# LnControlPanel.net
KiCad netlist of a schematic drawn in EAGLE
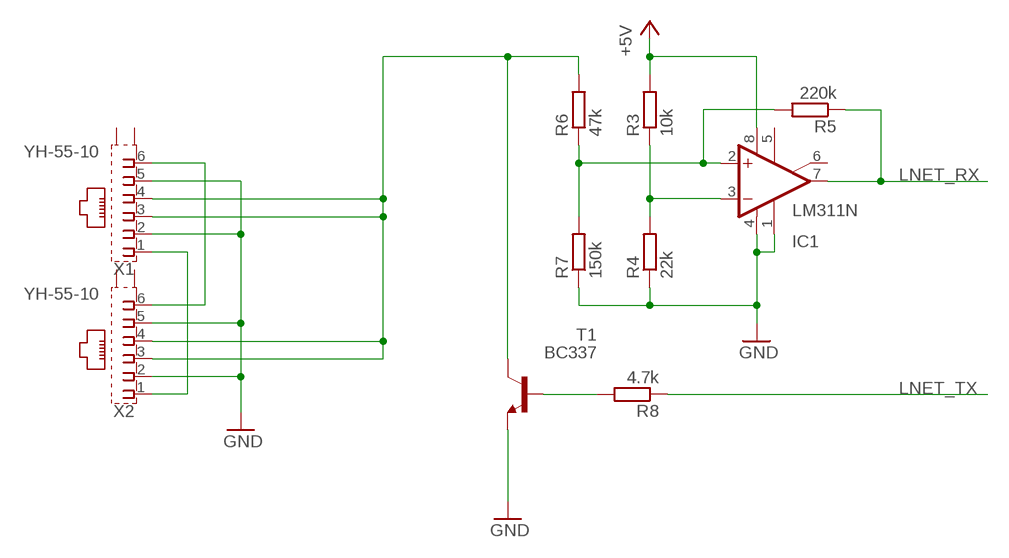
[diagram p0: schematic, sheet 1]
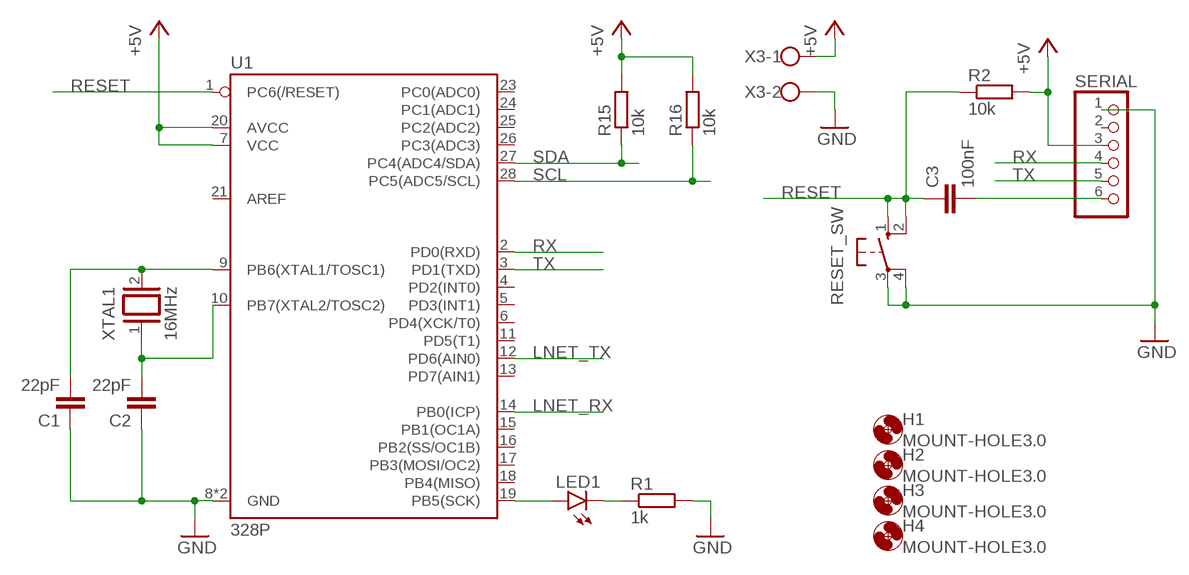
[diagram p1: schematic, sheet 2]
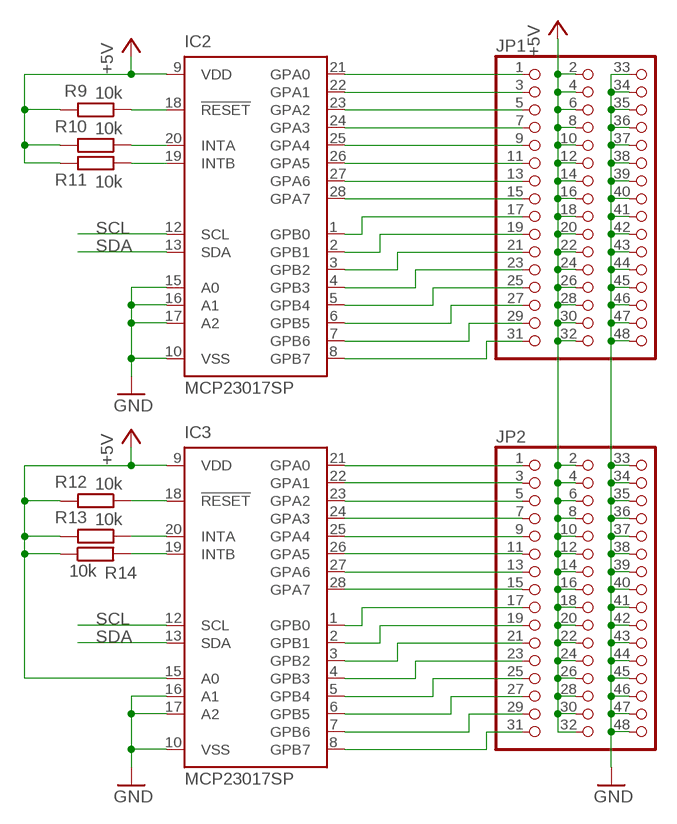
[diagram p2: schematic, sheet 3]

(export (version "E")
  (design (tool "Eeschema 10.0.6"))
  (components
    (comp (ref "C1")
      (value "22pF")
      (footprint "eagle-import:C025-025X050")
      (libsource (lib "eagle-import") (part "C-EU025-025X050"))
    )
    (comp (ref "C2")
      (value "22pF")
      (footprint "eagle-import:C025-025X050")
      (libsource (lib "eagle-import") (part "C-EU025-025X050"))
    )
    (comp (ref "C3")
      (value "100nF")
      (footprint "eagle-import:C050-030X075")
      (libsource (lib "eagle-import") (part "C-EU050-030X075"))
    )
    (comp (ref "H1")
      (value "MOUNT-HOLE3.0")
      (footprint "eagle-import:3,0")
      (libsource (lib "eagle-import") (part "MOUNT-HOLE3.0"))
    )
    (comp (ref "H2")
      (value "MOUNT-HOLE3.0")
      (footprint "eagle-import:3,0")
      (libsource (lib "eagle-import") (part "MOUNT-HOLE3.0"))
    )
    (comp (ref "H3")
      (value "MOUNT-HOLE3.0")
      (footprint "eagle-import:3,0")
      (libsource (lib "eagle-import") (part "MOUNT-HOLE3.0"))
    )
    (comp (ref "H4")
      (value "MOUNT-HOLE3.0")
      (footprint "eagle-import:3,0")
      (libsource (lib "eagle-import") (part "MOUNT-HOLE3.0"))
    )
    (comp (ref "LED1")
      (value "LED3MM")
      (footprint "eagle-import:LED3MM")
      (libsource (lib "eagle-import") (part "LED3MM"))
    )
    (comp (ref "R1")
      (value "1k")
      (footprint "eagle-import:0207_2V")
      (libsource (lib "eagle-import") (part "rcl_334_R-EU_0207/2V"))
    )
    (comp (ref "R2")
      (value "10k")
      (footprint "eagle-import:0207_2V")
      (libsource (lib "eagle-import") (part "rcl_334_R-EU_0207/2V"))
    )
    (comp (ref "R15")
      (value "10k")
      (footprint "eagle-import:0207_2V")
      (libsource (lib "eagle-import") (part "rcl_334_R-EU_0207/2V"))
    )
    (comp (ref "R16")
      (value "10k")
      (footprint "eagle-import:0207_2V")
      (libsource (lib "eagle-import") (part "rcl_334_R-EU_0207/2V"))
    )
    (comp (ref "RESET_SW")
      (value "10-XX")
      (footprint "eagle-import:B3F-10XX")
      (fields (field (name "MPN") "B3F-1000"))
      (libsource (lib "eagle-import") (part "10-XX"))
    )
    (comp (ref "SERIAL")
      (value "PINHD-1X6")
      (footprint "eagle-import:1X06")
      (libsource (lib "eagle-import") (part "PINHD-1X6"))
    )
    (comp (ref "U1")
      (value "328P")
      (footprint "eagle-import:DIP28")
      (libsource (lib "eagle-import") (part "ATMEGA328P_PDIP"))
    )
    (comp (ref "X3")
      (value "W237-102")
      (footprint "eagle-import:W237-102")
      (fields (field (name "MPN") "237-102"))
      (libsource (lib "eagle-import") (part "W237-102"))
    )
    (comp (ref "XTAL1")
      (value "16MHz")
      (footprint "eagle-import:QS")
      (libsource (lib "eagle-import") (part "XTAL/S"))
    )
    (comp (ref "IC2")
      (value "MCP23017SP")
      (footprint "eagle-import:DIL28-3")
      (fields (field (name "MF") "MICROCHIP") (field (name "MPN") "MCP23017-E/SP"))
      (libsource (lib "eagle-import") (part "MCP23017SP"))
    )
    (comp (ref "IC3")
      (value "MCP23017SP")
      (footprint "eagle-import:DIL28-3")
      (fields (field (name "MF") "MICROCHIP") (field (name "MPN") "MCP23017-E/SP"))
      (libsource (lib "eagle-import") (part "MCP23017SP"))
    )
    (comp (ref "JP1")
      (value "PINHD-3X16")
      (footprint "eagle-import:3X16")
      (libsource (lib "eagle-import") (part "PINHD-3X16"))
    )
    (comp (ref "JP2")
      (value "PINHD-3X16")
      (footprint "eagle-import:3X16")
      (libsource (lib "eagle-import") (part "PINHD-3X16"))
    )
    (comp (ref "R9")
      (value "10k")
      (footprint "eagle-import:0207_2V")
      (libsource (lib "eagle-import") (part "R-EU_0207/2V"))
    )
    (comp (ref "R10")
      (value "10k")
      (footprint "eagle-import:0207_2V")
      (libsource (lib "eagle-import") (part "R-EU_0207/2V"))
    )
    (comp (ref "R11")
      (value "10k")
      (footprint "eagle-import:0207_2V")
      (libsource (lib "eagle-import") (part "R-EU_0207/2V"))
    )
    (comp (ref "R12")
      (value "10k")
      (footprint "eagle-import:0207_2V")
      (libsource (lib "eagle-import") (part "R-EU_0207/2V"))
    )
    (comp (ref "R13")
      (value "10k")
      (footprint "eagle-import:0207_2V")
      (libsource (lib "eagle-import") (part "R-EU_0207/2V"))
    )
    (comp (ref "R14")
      (value "10k")
      (footprint "eagle-import:0207_2V")
      (libsource (lib "eagle-import") (part "R-EU_0207/2V"))
    )
    (comp (ref "IC1")
      (value "LM311N")
      (footprint "eagle-import:DIL08")
      (libsource (lib "eagle-import") (part "LM311N"))
    )
    (comp (ref "R3")
      (value "10k")
      (footprint "eagle-import:0207_2V")
      (libsource (lib "eagle-import") (part "R-EU_0207/2V"))
    )
    (comp (ref "R4")
      (value "22k")
      (footprint "eagle-import:0207_2V")
      (libsource (lib "eagle-import") (part "R-EU_0207/2V"))
    )
    (comp (ref "R5")
      (value "220k")
      (footprint "eagle-import:0207_2V")
      (libsource (lib "eagle-import") (part "R-EU_0207/2V"))
    )
    (comp (ref "R6")
      (value "47k")
      (footprint "eagle-import:0207_2V")
      (libsource (lib "eagle-import") (part "R-EU_0207/2V"))
    )
    (comp (ref "R7")
      (value "150k")
      (footprint "eagle-import:0207_2V")
      (libsource (lib "eagle-import") (part "R-EU_0207/2V"))
    )
    (comp (ref "R8")
      (value "4.7k")
      (footprint "eagle-import:0207_2V")
      (libsource (lib "eagle-import") (part "R-EU_0207/2V"))
    )
    (comp (ref "T1")
      (value "BC337")
      (footprint "eagle-import:TO92")
      (libsource (lib "eagle-import") (part "BC337"))
    )
    (comp (ref "X1")
      (value "YH-55-10")
      (footprint "eagle-import:YH-55-10")
      (libsource (lib "eagle-import") (part "YH-55-10"))
    )
    (comp (ref "X2")
      (value "YH-55-10")
      (footprint "eagle-import:YH-55-10")
      (libsource (lib "eagle-import") (part "YH-55-10"))
    )
  )
  (nets
    (net (code "1") (name "+5V") (class "Default")
      (node (ref "IC1") (pin "8") (pinfunction "V+_8") (pintype "power_in"))
      (node (ref "IC2") (pin "9") (pinfunction "VDD_9") (pintype "power_in"))
      (node (ref "IC3") (pin "15") (pinfunction "A0_15") (pintype "input"))
      (node (ref "IC3") (pin "9") (pinfunction "VDD_9") (pintype "power_in"))
      (node (ref "JP1") (pin "10") (pinfunction "10_10") (pintype "passive"))
      (node (ref "JP1") (pin "12") (pinfunction "12_12") (pintype "passive"))
      (node (ref "JP1") (pin "14") (pinfunction "14_14") (pintype "passive"))
      (node (ref "JP1") (pin "16") (pinfunction "16_16") (pintype "passive"))
      (node (ref "JP1") (pin "18") (pinfunction "18_18") (pintype "passive"))
      (node (ref "JP1") (pin "2") (pinfunction "2_2") (pintype "passive"))
      (node (ref "JP1") (pin "20") (pinfunction "20_20") (pintype "passive"))
      (node (ref "JP1") (pin "22") (pinfunction "22_22") (pintype "passive"))
      (node (ref "JP1") (pin "24") (pinfunction "24_24") (pintype "passive"))
      (node (ref "JP1") (pin "26") (pinfunction "26_26") (pintype "passive"))
      (node (ref "JP1") (pin "28") (pinfunction "28_28") (pintype "passive"))
      (node (ref "JP1") (pin "30") (pinfunction "30_30") (pintype "passive"))
      (node (ref "JP1") (pin "32") (pinfunction "32_32") (pintype "passive"))
      (node (ref "JP1") (pin "4") (pinfunction "4_4") (pintype "passive"))
      (node (ref "JP1") (pin "6") (pinfunction "6_6") (pintype "passive"))
      (node (ref "JP1") (pin "8") (pinfunction "8_8") (pintype "passive"))
      (node (ref "JP2") (pin "10") (pinfunction "10_10") (pintype "passive"))
      (node (ref "JP2") (pin "12") (pinfunction "12_12") (pintype "passive"))
      (node (ref "JP2") (pin "14") (pinfunction "14_14") (pintype "passive"))
      (node (ref "JP2") (pin "16") (pinfunction "16_16") (pintype "passive"))
      (node (ref "JP2") (pin "18") (pinfunction "18_18") (pintype "passive"))
      (node (ref "JP2") (pin "2") (pinfunction "2_2") (pintype "passive"))
      (node (ref "JP2") (pin "20") (pinfunction "20_20") (pintype "passive"))
      (node (ref "JP2") (pin "22") (pinfunction "22_22") (pintype "passive"))
      (node (ref "JP2") (pin "24") (pinfunction "24_24") (pintype "passive"))
      (node (ref "JP2") (pin "26") (pinfunction "26_26") (pintype "passive"))
      (node (ref "JP2") (pin "28") (pinfunction "28_28") (pintype "passive"))
      (node (ref "JP2") (pin "30") (pinfunction "30_30") (pintype "passive"))
      (node (ref "JP2") (pin "32") (pinfunction "32_32") (pintype "passive"))
      (node (ref "JP2") (pin "4") (pinfunction "4_4") (pintype "passive"))
      (node (ref "JP2") (pin "6") (pinfunction "6_6") (pintype "passive"))
      (node (ref "JP2") (pin "8") (pinfunction "8_8") (pintype "passive"))
      (node (ref "R10") (pin "2") (pinfunction "2_2") (pintype "passive"))
      (node (ref "R11") (pin "2") (pinfunction "2_2") (pintype "passive"))
      (node (ref "R12") (pin "2") (pinfunction "2_2") (pintype "passive"))
      (node (ref "R13") (pin "2") (pinfunction "2_2") (pintype "passive"))
      (node (ref "R14") (pin "1") (pinfunction "1_1") (pintype "passive"))
      (node (ref "R15") (pin "2") (pinfunction "2_2") (pintype "passive"))
      (node (ref "R16") (pin "2") (pinfunction "2_2") (pintype "passive"))
      (node (ref "R2") (pin "2") (pinfunction "2_2") (pintype "passive"))
      (node (ref "R3") (pin "2") (pinfunction "2_2") (pintype "passive"))
      (node (ref "R9") (pin "2") (pinfunction "2_2") (pintype "passive"))
      (node (ref "SERIAL") (pin "3") (pinfunction "3_3") (pintype "passive"))
      (node (ref "U1") (pin "20") (pinfunction "AVCC_20") (pintype "bidirectional"))
      (node (ref "U1") (pin "7") (pinfunction "VCC_7") (pintype "bidirectional"))
      (node (ref "X3") (pin "1") (pinfunction "KL_1") (pintype "passive"))
    )
    (net (code "2") (name "GND") (class "Default")
      (node (ref "C1") (pin "1") (pinfunction "1_1") (pintype "passive"))
      (node (ref "C2") (pin "1") (pinfunction "1_1") (pintype "passive"))
      (node (ref "IC1") (pin "1") (pinfunction "GND_1") (pintype "passive"))
      (node (ref "IC1") (pin "4") (pinfunction "V-_4") (pintype "power_in"))
      (node (ref "IC2") (pin "10") (pinfunction "VSS_10") (pintype "power_in"))
      (node (ref "IC2") (pin "15") (pinfunction "A0_15") (pintype "input"))
      (node (ref "IC2") (pin "16") (pinfunction "A1_16") (pintype "input"))
      (node (ref "IC2") (pin "17") (pinfunction "A2_17") (pintype "input"))
      (node (ref "IC3") (pin "10") (pinfunction "VSS_10") (pintype "power_in"))
      (node (ref "IC3") (pin "16") (pinfunction "A1_16") (pintype "input"))
      (node (ref "IC3") (pin "17") (pinfunction "A2_17") (pintype "input"))
      (node (ref "JP1") (pin "33") (pinfunction "33_33") (pintype "passive"))
      (node (ref "JP1") (pin "34") (pinfunction "34_34") (pintype "passive"))
      (node (ref "JP1") (pin "35") (pinfunction "35_35") (pintype "passive"))
      (node (ref "JP1") (pin "36") (pinfunction "36_36") (pintype "passive"))
      (node (ref "JP1") (pin "37") (pinfunction "37_37") (pintype "passive"))
      (node (ref "JP1") (pin "38") (pinfunction "38_38") (pintype "passive"))
      (node (ref "JP1") (pin "39") (pinfunction "39_39") (pintype "passive"))
      (node (ref "JP1") (pin "40") (pinfunction "40_40") (pintype "passive"))
      (node (ref "JP1") (pin "41") (pinfunction "41_41") (pintype "passive"))
      (node (ref "JP1") (pin "42") (pinfunction "42_42") (pintype "passive"))
      (node (ref "JP1") (pin "43") (pinfunction "43_43") (pintype "passive"))
      (node (ref "JP1") (pin "44") (pinfunction "44_44") (pintype "passive"))
      (node (ref "JP1") (pin "45") (pinfunction "45_45") (pintype "passive"))
      (node (ref "JP1") (pin "46") (pinfunction "46_46") (pintype "passive"))
      (node (ref "JP1") (pin "47") (pinfunction "47_47") (pintype "passive"))
      (node (ref "JP1") (pin "48") (pinfunction "48_48") (pintype "passive"))
      (node (ref "JP2") (pin "33") (pinfunction "33_33") (pintype "passive"))
      (node (ref "JP2") (pin "34") (pinfunction "34_34") (pintype "passive"))
      (node (ref "JP2") (pin "35") (pinfunction "35_35") (pintype "passive"))
      (node (ref "JP2") (pin "36") (pinfunction "36_36") (pintype "passive"))
      (node (ref "JP2") (pin "37") (pinfunction "37_37") (pintype "passive"))
      (node (ref "JP2") (pin "38") (pinfunction "38_38") (pintype "passive"))
      (node (ref "JP2") (pin "39") (pinfunction "39_39") (pintype "passive"))
      (node (ref "JP2") (pin "40") (pinfunction "40_40") (pintype "passive"))
      (node (ref "JP2") (pin "41") (pinfunction "41_41") (pintype "passive"))
      (node (ref "JP2") (pin "42") (pinfunction "42_42") (pintype "passive"))
      (node (ref "JP2") (pin "43") (pinfunction "43_43") (pintype "passive"))
      (node (ref "JP2") (pin "44") (pinfunction "44_44") (pintype "passive"))
      (node (ref "JP2") (pin "45") (pinfunction "45_45") (pintype "passive"))
      (node (ref "JP2") (pin "46") (pinfunction "46_46") (pintype "passive"))
      (node (ref "JP2") (pin "47") (pinfunction "47_47") (pintype "passive"))
      (node (ref "JP2") (pin "48") (pinfunction "48_48") (pintype "passive"))
      (node (ref "R1") (pin "2") (pinfunction "2_2") (pintype "passive"))
      (node (ref "R4") (pin "1") (pinfunction "1_1") (pintype "passive"))
      (node (ref "R7") (pin "1") (pinfunction "1_1") (pintype "passive"))
      (node (ref "RESET_SW") (pin "3") (pinfunction "P_3") (pintype "passive"))
      (node (ref "RESET_SW") (pin "4") (pinfunction "P1_4") (pintype "passive"))
      (node (ref "SERIAL") (pin "1") (pinfunction "1_1") (pintype "passive"))
      (node (ref "T1") (pin "1") (pinfunction "E_1") (pintype "passive"))
      (node (ref "U1") (pin "22") (pinfunction "GND_22") (pintype "bidirectional"))
      (node (ref "U1") (pin "8") (pinfunction "GND_8") (pintype "bidirectional"))
      (node (ref "X1") (pin "2") (pinfunction "2_2") (pintype "passive"))
      (node (ref "X1") (pin "5") (pinfunction "5_5") (pintype "passive"))
      (node (ref "X2") (pin "2") (pinfunction "2_2") (pintype "passive"))
      (node (ref "X2") (pin "5") (pinfunction "5_5") (pintype "passive"))
      (node (ref "X3") (pin "2") (pinfunction "KL_2") (pintype "passive"))
    )
    (net (code "3") (name "LNET_RX") (class "Default")
      (node (ref "IC1") (pin "7") (pinfunction "OUT_7") (pintype "output"))
      (node (ref "R5") (pin "1") (pinfunction "1_1") (pintype "passive"))
      (node (ref "U1") (pin "14") (pinfunction "PB0(ICP)_14") (pintype "bidirectional"))
    )
    (net (code "4") (name "LNET_TX") (class "Default")
      (node (ref "R8") (pin "1") (pinfunction "1_1") (pintype "passive"))
      (node (ref "U1") (pin "12") (pinfunction "PD6(AIN0)_12") (pintype "bidirectional"))
    )
    (net (code "5") (name "Net-(C3-Pad2)") (class "Default")
      (node (ref "C3") (pin "2") (pinfunction "2_2") (pintype "passive"))
      (node (ref "SERIAL") (pin "6") (pinfunction "6_6") (pintype "passive"))
    )
    (net (code "6") (name "Net-(IC1-+IN)") (class "Default")
      (node (ref "IC1") (pin "2") (pinfunction "+IN_2") (pintype "input"))
      (node (ref "R5") (pin "2") (pinfunction "2_2") (pintype "passive"))
      (node (ref "R6") (pin "1") (pinfunction "1_1") (pintype "passive"))
      (node (ref "R7") (pin "2") (pinfunction "2_2") (pintype "passive"))
    )
    (net (code "7") (name "Net-(IC1--IN)") (class "Default")
      (node (ref "IC1") (pin "3") (pinfunction "-IN_3") (pintype "input"))
      (node (ref "R3") (pin "1") (pinfunction "1_1") (pintype "passive"))
      (node (ref "R4") (pin "2") (pinfunction "2_2") (pintype "passive"))
    )
    (net (code "8") (name "Net-(IC2-GPA0)") (class "Default")
      (node (ref "IC2") (pin "21") (pinfunction "GPA0_21") (pintype "bidirectional"))
      (node (ref "JP1") (pin "1") (pinfunction "1_1") (pintype "passive"))
    )
    (net (code "9") (name "Net-(IC2-GPA1)") (class "Default")
      (node (ref "IC2") (pin "22") (pinfunction "GPA1_22") (pintype "bidirectional"))
      (node (ref "JP1") (pin "3") (pinfunction "3_3") (pintype "passive"))
    )
    (net (code "10") (name "Net-(IC2-GPA2)") (class "Default")
      (node (ref "IC2") (pin "23") (pinfunction "GPA2_23") (pintype "bidirectional"))
      (node (ref "JP1") (pin "5") (pinfunction "5_5") (pintype "passive"))
    )
    (net (code "11") (name "Net-(IC2-GPA3)") (class "Default")
      (node (ref "IC2") (pin "24") (pinfunction "GPA3_24") (pintype "bidirectional"))
      (node (ref "JP1") (pin "7") (pinfunction "7_7") (pintype "passive"))
    )
    (net (code "12") (name "Net-(IC2-GPA4)") (class "Default")
      (node (ref "IC2") (pin "25") (pinfunction "GPA4_25") (pintype "bidirectional"))
      (node (ref "JP1") (pin "9") (pinfunction "9_9") (pintype "passive"))
    )
    (net (code "13") (name "Net-(IC2-GPA5)") (class "Default")
      (node (ref "IC2") (pin "26") (pinfunction "GPA5_26") (pintype "bidirectional"))
      (node (ref "JP1") (pin "11") (pinfunction "11_11") (pintype "passive"))
    )
    (net (code "14") (name "Net-(IC2-GPA6)") (class "Default")
      (node (ref "IC2") (pin "27") (pinfunction "GPA6_27") (pintype "bidirectional"))
      (node (ref "JP1") (pin "13") (pinfunction "13_13") (pintype "passive"))
    )
    (net (code "15") (name "Net-(IC2-GPA7)") (class "Default")
      (node (ref "IC2") (pin "28") (pinfunction "GPA7_28") (pintype "bidirectional"))
      (node (ref "JP1") (pin "15") (pinfunction "15_15") (pintype "passive"))
    )
    (net (code "16") (name "Net-(IC2-GPB0)") (class "Default")
      (node (ref "IC2") (pin "1") (pinfunction "GPB0_1") (pintype "bidirectional"))
      (node (ref "JP1") (pin "17") (pinfunction "17_17") (pintype "passive"))
    )
    (net (code "17") (name "Net-(IC2-GPB1)") (class "Default")
      (node (ref "IC2") (pin "2") (pinfunction "GPB1_2") (pintype "bidirectional"))
      (node (ref "JP1") (pin "19") (pinfunction "19_19") (pintype "passive"))
    )
    (net (code "18") (name "Net-(IC2-GPB2)") (class "Default")
      (node (ref "IC2") (pin "3") (pinfunction "GPB2_3") (pintype "bidirectional"))
      (node (ref "JP1") (pin "21") (pinfunction "21_21") (pintype "passive"))
    )
    (net (code "19") (name "Net-(IC2-GPB3)") (class "Default")
      (node (ref "IC2") (pin "4") (pinfunction "GPB3_4") (pintype "bidirectional"))
      (node (ref "JP1") (pin "23") (pinfunction "23_23") (pintype "passive"))
    )
    (net (code "20") (name "Net-(IC2-GPB4)") (class "Default")
      (node (ref "IC2") (pin "5") (pinfunction "GPB4_5") (pintype "bidirectional"))
      (node (ref "JP1") (pin "25") (pinfunction "25_25") (pintype "passive"))
    )
    (net (code "21") (name "Net-(IC2-GPB5)") (class "Default")
      (node (ref "IC2") (pin "6") (pinfunction "GPB5_6") (pintype "bidirectional"))
      (node (ref "JP1") (pin "27") (pinfunction "27_27") (pintype "passive"))
    )
    (net (code "22") (name "Net-(IC2-GPB6)") (class "Default")
      (node (ref "IC2") (pin "7") (pinfunction "GPB6_7") (pintype "bidirectional"))
      (node (ref "JP1") (pin "29") (pinfunction "29_29") (pintype "passive"))
    )
    (net (code "23") (name "Net-(IC2-GPB7)") (class "Default")
      (node (ref "IC2") (pin "8") (pinfunction "GPB7_8") (pintype "bidirectional"))
      (node (ref "JP1") (pin "31") (pinfunction "31_31") (pintype "passive"))
    )
    (net (code "24") (name "Net-(IC2-INTA)") (class "Default")
      (node (ref "IC2") (pin "20") (pinfunction "INTA_20") (pintype "output"))
      (node (ref "R10") (pin "1") (pinfunction "1_1") (pintype "passive"))
    )
    (net (code "25") (name "Net-(IC2-INTB)") (class "Default")
      (node (ref "IC2") (pin "19") (pinfunction "INTB_19") (pintype "output"))
      (node (ref "R11") (pin "1") (pinfunction "1_1") (pintype "passive"))
    )
    (net (code "26") (name "Net-(IC2-~{RESET})") (class "Default")
      (node (ref "IC2") (pin "18") (pinfunction "~{RESET}_18") (pintype "input"))
      (node (ref "R9") (pin "1") (pinfunction "1_1") (pintype "passive"))
    )
    (net (code "27") (name "Net-(IC3-GPA0)") (class "Default")
      (node (ref "IC3") (pin "21") (pinfunction "GPA0_21") (pintype "bidirectional"))
      (node (ref "JP2") (pin "1") (pinfunction "1_1") (pintype "passive"))
    )
    (net (code "28") (name "Net-(IC3-GPA1)") (class "Default")
      (node (ref "IC3") (pin "22") (pinfunction "GPA1_22") (pintype "bidirectional"))
      (node (ref "JP2") (pin "3") (pinfunction "3_3") (pintype "passive"))
    )
    (net (code "29") (name "Net-(IC3-GPA2)") (class "Default")
      (node (ref "IC3") (pin "23") (pinfunction "GPA2_23") (pintype "bidirectional"))
      (node (ref "JP2") (pin "5") (pinfunction "5_5") (pintype "passive"))
    )
    (net (code "30") (name "Net-(IC3-GPA3)") (class "Default")
      (node (ref "IC3") (pin "24") (pinfunction "GPA3_24") (pintype "bidirectional"))
      (node (ref "JP2") (pin "7") (pinfunction "7_7") (pintype "passive"))
    )
    (net (code "31") (name "Net-(IC3-GPA4)") (class "Default")
      (node (ref "IC3") (pin "25") (pinfunction "GPA4_25") (pintype "bidirectional"))
      (node (ref "JP2") (pin "9") (pinfunction "9_9") (pintype "passive"))
    )
    (net (code "32") (name "Net-(IC3-GPA5)") (class "Default")
      (node (ref "IC3") (pin "26") (pinfunction "GPA5_26") (pintype "bidirectional"))
      (node (ref "JP2") (pin "11") (pinfunction "11_11") (pintype "passive"))
    )
    (net (code "33") (name "Net-(IC3-GPA6)") (class "Default")
      (node (ref "IC3") (pin "27") (pinfunction "GPA6_27") (pintype "bidirectional"))
      (node (ref "JP2") (pin "13") (pinfunction "13_13") (pintype "passive"))
    )
    (net (code "34") (name "Net-(IC3-GPA7)") (class "Default")
      (node (ref "IC3") (pin "28") (pinfunction "GPA7_28") (pintype "bidirectional"))
      (node (ref "JP2") (pin "15") (pinfunction "15_15") (pintype "passive"))
    )
    (net (code "35") (name "Net-(IC3-GPB0)") (class "Default")
      (node (ref "IC3") (pin "1") (pinfunction "GPB0_1") (pintype "bidirectional"))
      (node (ref "JP2") (pin "17") (pinfunction "17_17") (pintype "passive"))
    )
    (net (code "36") (name "Net-(IC3-GPB1)") (class "Default")
      (node (ref "IC3") (pin "2") (pinfunction "GPB1_2") (pintype "bidirectional"))
      (node (ref "JP2") (pin "19") (pinfunction "19_19") (pintype "passive"))
    )
    (net (code "37") (name "Net-(IC3-GPB2)") (class "Default")
      (node (ref "IC3") (pin "3") (pinfunction "GPB2_3") (pintype "bidirectional"))
      (node (ref "JP2") (pin "21") (pinfunction "21_21") (pintype "passive"))
    )
    (net (code "38") (name "Net-(IC3-GPB3)") (class "Default")
      (node (ref "IC3") (pin "4") (pinfunction "GPB3_4") (pintype "bidirectional"))
      (node (ref "JP2") (pin "23") (pinfunction "23_23") (pintype "passive"))
    )
    (net (code "39") (name "Net-(IC3-GPB4)") (class "Default")
      (node (ref "IC3") (pin "5") (pinfunction "GPB4_5") (pintype "bidirectional"))
      (node (ref "JP2") (pin "25") (pinfunction "25_25") (pintype "passive"))
    )
    (net (code "40") (name "Net-(IC3-GPB5)") (class "Default")
      (node (ref "IC3") (pin "6") (pinfunction "GPB5_6") (pintype "bidirectional"))
      (node (ref "JP2") (pin "27") (pinfunction "27_27") (pintype "passive"))
    )
    (net (code "41") (name "Net-(IC3-GPB6)") (class "Default")
      (node (ref "IC3") (pin "7") (pinfunction "GPB6_7") (pintype "bidirectional"))
      (node (ref "JP2") (pin "29") (pinfunction "29_29") (pintype "passive"))
    )
    (net (code "42") (name "Net-(IC3-GPB7)") (class "Default")
      (node (ref "IC3") (pin "8") (pinfunction "GPB7_8") (pintype "bidirectional"))
      (node (ref "JP2") (pin "31") (pinfunction "31_31") (pintype "passive"))
    )
    (net (code "43") (name "Net-(IC3-INTA)") (class "Default")
      (node (ref "IC3") (pin "20") (pinfunction "INTA_20") (pintype "output"))
      (node (ref "R13") (pin "1") (pinfunction "1_1") (pintype "passive"))
    )
    (net (code "44") (name "Net-(IC3-INTB)") (class "Default")
      (node (ref "IC3") (pin "19") (pinfunction "INTB_19") (pintype "output"))
      (node (ref "R14") (pin "2") (pinfunction "2_2") (pintype "passive"))
    )
    (net (code "45") (name "Net-(IC3-~{RESET})") (class "Default")
      (node (ref "IC3") (pin "18") (pinfunction "~{RESET}_18") (pintype "input"))
      (node (ref "R12") (pin "1") (pinfunction "1_1") (pintype "passive"))
    )
    (net (code "46") (name "Net-(LED1-C)") (class "Default")
      (node (ref "LED1") (pin "K") (pinfunction "C_K") (pintype "passive"))
      (node (ref "R1") (pin "1") (pinfunction "1_1") (pintype "passive"))
    )
    (net (code "47") (name "Net-(T1-B)") (class "Default")
      (node (ref "R8") (pin "2") (pinfunction "2_2") (pintype "passive"))
      (node (ref "T1") (pin "2") (pinfunction "B_2") (pintype "passive"))
    )
    (net (code "48") (name "Net-(T1-C)") (class "Default")
      (node (ref "R6") (pin "2") (pinfunction "2_2") (pintype "passive"))
      (node (ref "T1") (pin "3") (pinfunction "C_3") (pintype "passive"))
      (node (ref "X1") (pin "3") (pinfunction "3_3") (pintype "passive"))
      (node (ref "X1") (pin "4") (pinfunction "4_4") (pintype "passive"))
      (node (ref "X2") (pin "3") (pinfunction "3_3") (pintype "passive"))
      (node (ref "X2") (pin "4") (pinfunction "4_4") (pintype "passive"))
    )
    (net (code "49") (name "Net-(U1-PB5(SCK))") (class "Default")
      (node (ref "LED1") (pin "A") (pinfunction "A_A") (pintype "passive"))
      (node (ref "U1") (pin "19") (pinfunction "PB5(SCK)_19") (pintype "bidirectional"))
    )
    (net (code "50") (name "Net-(U1-PB6(XTAL1{slash}TOSC1))") (class "Default")
      (node (ref "C1") (pin "2") (pinfunction "2_2") (pintype "passive"))
      (node (ref "U1") (pin "9") (pinfunction "PB6(XTAL1/TOSC1)_9") (pintype "bidirectional"))
      (node (ref "XTAL1") (pin "2") (pinfunction "2_2") (pintype "passive"))
    )
    (net (code "51") (name "Net-(U1-PB7(XTAL2{slash}TOSC2))") (class "Default")
      (node (ref "C2") (pin "2") (pinfunction "2_2") (pintype "passive"))
      (node (ref "U1") (pin "10") (pinfunction "PB7(XTAL2/TOSC2)_10") (pintype "bidirectional"))
      (node (ref "XTAL1") (pin "1") (pinfunction "1_1") (pintype "passive"))
    )
    (net (code "52") (name "Net-(X1-Pad1)") (class "Default")
      (node (ref "X1") (pin "1") (pinfunction "1_1") (pintype "passive"))
      (node (ref "X2") (pin "1") (pinfunction "1_1") (pintype "passive"))
    )
    (net (code "53") (name "Net-(X1-Pad6)") (class "Default")
      (node (ref "X1") (pin "6") (pinfunction "6_6") (pintype "passive"))
      (node (ref "X2") (pin "6") (pinfunction "6_6") (pintype "passive"))
    )
    (net (code "54") (name "RESET") (class "Default")
      (node (ref "C3") (pin "1") (pinfunction "1_1") (pintype "passive"))
      (node (ref "R2") (pin "1") (pinfunction "1_1") (pintype "passive"))
      (node (ref "RESET_SW") (pin "1") (pinfunction "S_1") (pintype "passive"))
      (node (ref "RESET_SW") (pin "2") (pinfunction "S1_2") (pintype "passive"))
      (node (ref "U1") (pin "1") (pinfunction "PC6(/RESET)_1") (pintype "bidirectional"))
    )
    (net (code "55") (name "RX") (class "Default")
      (node (ref "SERIAL") (pin "4") (pinfunction "4_4") (pintype "passive"))
      (node (ref "U1") (pin "2") (pinfunction "PD0(RXD)_2") (pintype "bidirectional"))
    )
    (net (code "56") (name "SCL") (class "Default")
      (node (ref "IC2") (pin "12") (pinfunction "SCL_12") (pintype "input"))
      (node (ref "IC3") (pin "12") (pinfunction "SCL_12") (pintype "input"))
      (node (ref "R16") (pin "1") (pinfunction "1_1") (pintype "passive"))
      (node (ref "U1") (pin "28") (pinfunction "PC5(ADC5/SCL)_28") (pintype "bidirectional"))
    )
    (net (code "57") (name "SDA") (class "Default")
      (node (ref "IC2") (pin "13") (pinfunction "SDA_13") (pintype "bidirectional"))
      (node (ref "IC3") (pin "13") (pinfunction "SDA_13") (pintype "bidirectional"))
      (node (ref "R15") (pin "1") (pinfunction "1_1") (pintype "passive"))
      (node (ref "U1") (pin "27") (pinfunction "PC4(ADC4/SDA)_27") (pintype "bidirectional"))
    )
    (net (code "58") (name "TX") (class "Default")
      (node (ref "SERIAL") (pin "5") (pinfunction "5_5") (pintype "passive"))
      (node (ref "U1") (pin "3") (pinfunction "PD1(TXD)_3") (pintype "bidirectional"))
    )
    (net (code "59") (name "unconnected-(IC1-ON-Pad5)") (class "Default")
      (node (ref "IC1") (pin "5") (pinfunction "ON_5") (pintype "passive"))
    )
    (net (code "60") (name "unconnected-(IC1-ON{slash}STR-Pad6)") (class "Default")
      (node (ref "IC1") (pin "6") (pinfunction "ON/STR_6") (pintype "passive"))
    )
    (net (code "61") (name "unconnected-(SERIAL-Pad2)") (class "Default")
      (node (ref "SERIAL") (pin "2") (pinfunction "2_2") (pintype "passive"))
    )
    (net (code "62") (name "unconnected-(U1-AREF-Pad21)") (class "Default")
      (node (ref "U1") (pin "21") (pinfunction "AREF_21") (pintype "bidirectional"))
    )
    (net (code "63") (name "unconnected-(U1-PB1(OC1A)-Pad15)") (class "Default")
      (node (ref "U1") (pin "15") (pinfunction "PB1(OC1A)_15") (pintype "bidirectional"))
    )
    (net (code "64") (name "unconnected-(U1-PB2(SS{slash}OC1B)-Pad16)") (class "Default")
      (node (ref "U1") (pin "16") (pinfunction "PB2(SS/OC1B)_16") (pintype "bidirectional"))
    )
    (net (code "65") (name "unconnected-(U1-PB3(MOSI{slash}OC2)-Pad17)") (class "Default")
      (node (ref "U1") (pin "17") (pinfunction "PB3(MOSI/OC2)_17") (pintype "bidirectional"))
    )
    (net (code "66") (name "unconnected-(U1-PB4(MISO)-Pad18)") (class "Default")
      (node (ref "U1") (pin "18") (pinfunction "PB4(MISO)_18") (pintype "bidirectional"))
    )
    (net (code "67") (name "unconnected-(U1-PC0(ADC0)-Pad23)") (class "Default")
      (node (ref "U1") (pin "23") (pinfunction "PC0(ADC0)_23") (pintype "bidirectional"))
    )
    (net (code "68") (name "unconnected-(U1-PC1(ADC1)-Pad24)") (class "Default")
      (node (ref "U1") (pin "24") (pinfunction "PC1(ADC1)_24") (pintype "bidirectional"))
    )
    (net (code "69") (name "unconnected-(U1-PC2(ADC2)-Pad25)") (class "Default")
      (node (ref "U1") (pin "25") (pinfunction "PC2(ADC2)_25") (pintype "bidirectional"))
    )
    (net (code "70") (name "unconnected-(U1-PC3(ADC3)-Pad26)") (class "Default")
      (node (ref "U1") (pin "26") (pinfunction "PC3(ADC3)_26") (pintype "bidirectional"))
    )
    (net (code "71") (name "unconnected-(U1-PD2(INT0)-Pad4)") (class "Default")
      (node (ref "U1") (pin "4") (pinfunction "PD2(INT0)_4") (pintype "bidirectional"))
    )
    (net (code "72") (name "unconnected-(U1-PD3(INT1)-Pad5)") (class "Default")
      (node (ref "U1") (pin "5") (pinfunction "PD3(INT1)_5") (pintype "bidirectional"))
    )
    (net (code "73") (name "unconnected-(U1-PD4(XCK{slash}T0)-Pad6)") (class "Default")
      (node (ref "U1") (pin "6") (pinfunction "PD4(XCK/T0)_6") (pintype "bidirectional"))
    )
    (net (code "74") (name "unconnected-(U1-PD5(T1)-Pad11)") (class "Default")
      (node (ref "U1") (pin "11") (pinfunction "PD5(T1)_11") (pintype "bidirectional"))
    )
    (net (code "75") (name "unconnected-(U1-PD7(AIN1)-Pad13)") (class "Default")
      (node (ref "U1") (pin "13") (pinfunction "PD7(AIN1)_13") (pintype "bidirectional"))
    )
    (net (code "76") (name "unconnected-(X1-S-PadS1)") (class "Default")
      (node (ref "X1") (pin "S1") (pinfunction "S_S1") (pintype "passive"))
    )
    (net (code "77") (name "unconnected-(X1-S-PadS2)") (class "Default")
      (node (ref "X1") (pin "S2") (pinfunction "S_S2") (pintype "passive"))
    )
    (net (code "78") (name "unconnected-(X2-S-PadS1)") (class "Default")
      (node (ref "X2") (pin "S1") (pinfunction "S_S1") (pintype "passive"))
    )
    (net (code "79") (name "unconnected-(X2-S-PadS2)") (class "Default")
      (node (ref "X2") (pin "S2") (pinfunction "S_S2") (pintype "passive"))
    )
  )
)
